# SHT10-Adapter.net
KiCad netlist of a schematic drawn in EAGLE
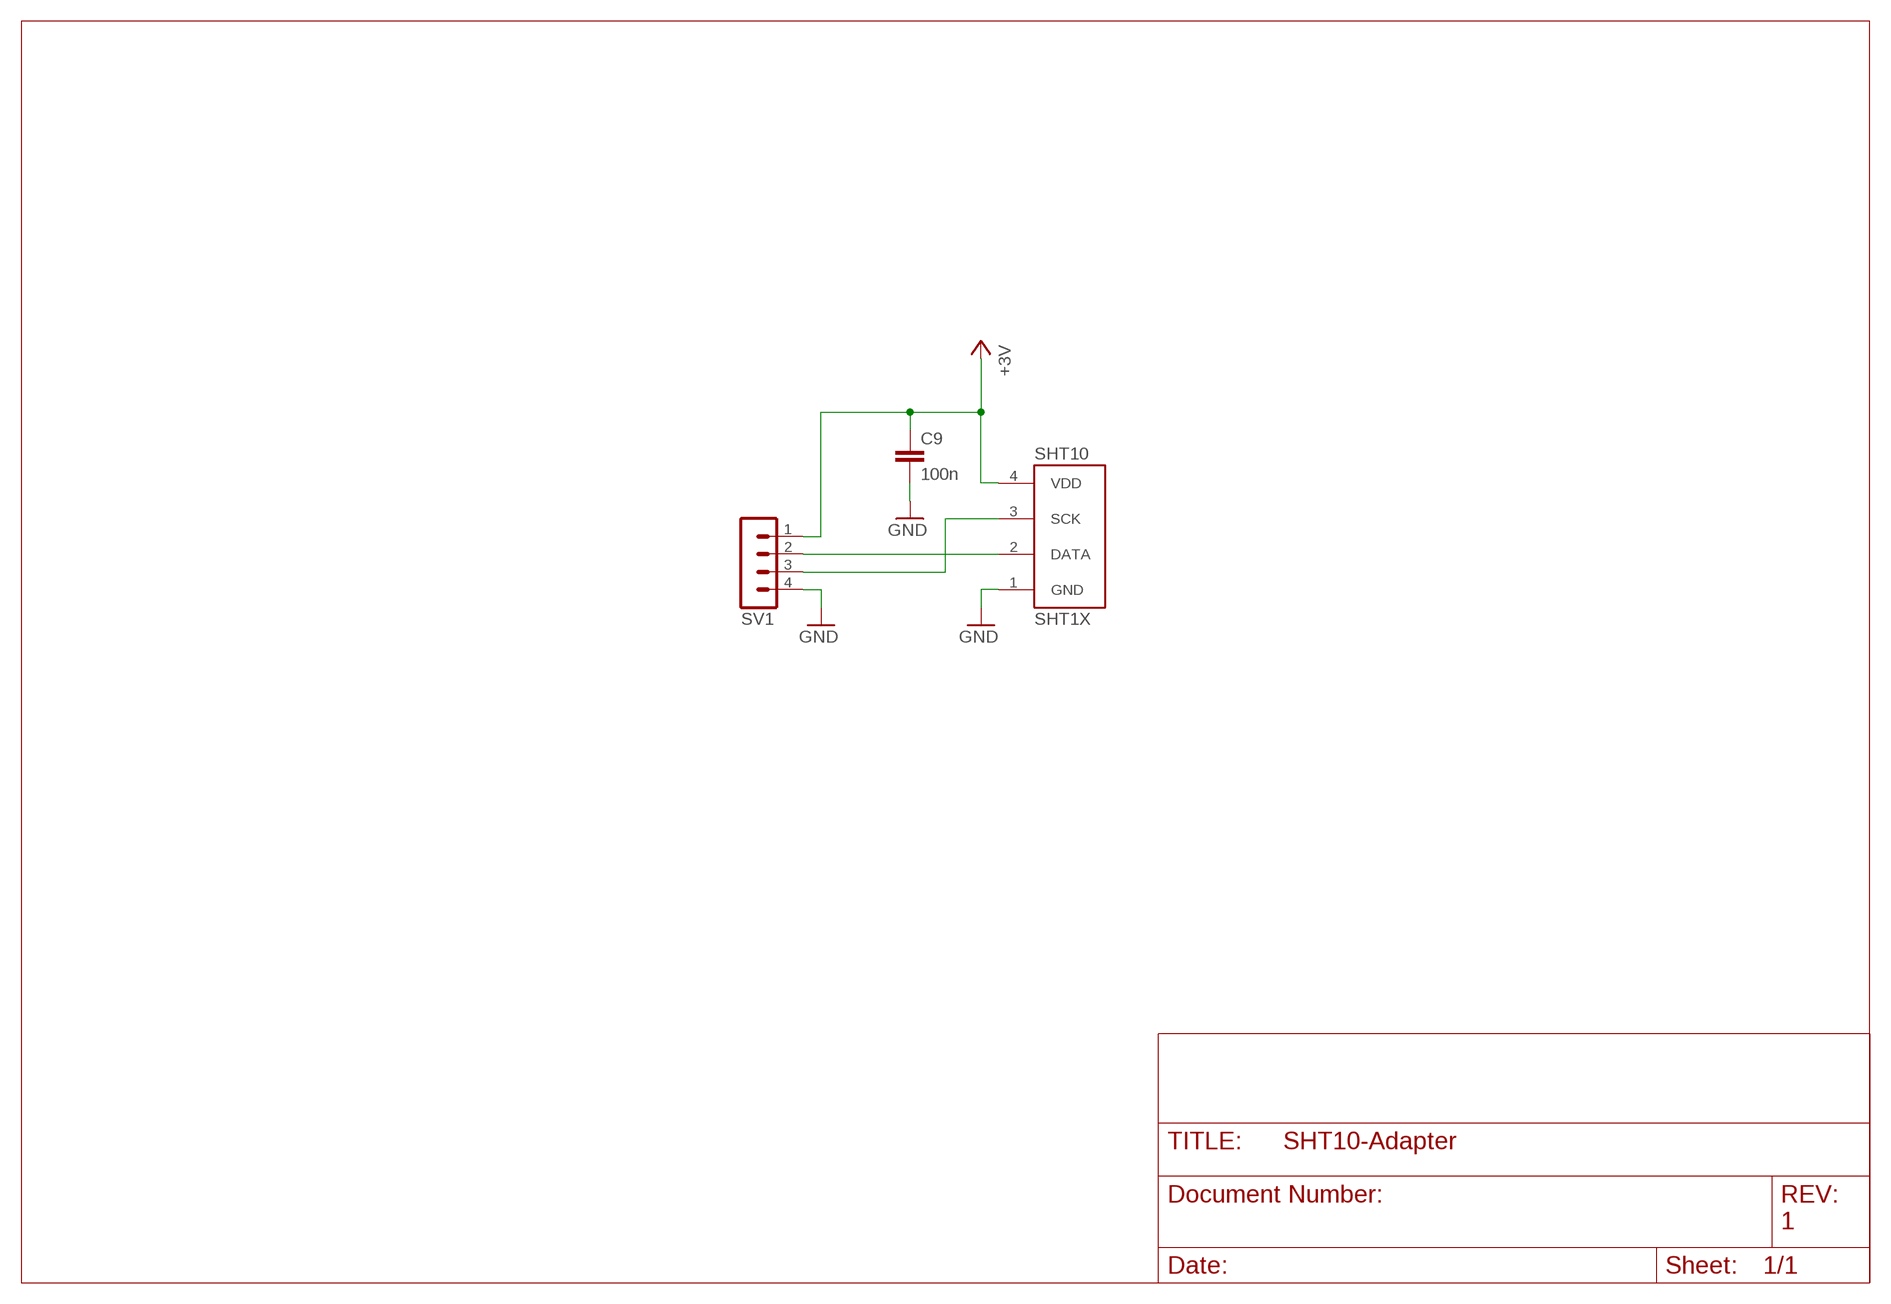
[diagram p0: schematic, sheet 1]

(export (version "E")
  (design (tool "Eeschema 10.0.6"))
  (components
    (comp (ref "C9")
      (value "100n")
      (footprint "eagle-import:C0805")
      (libsource (lib "eagle-import") (part "C-EUC0805"))
    )
    (comp (ref "SHT10")
      (value "SHT1X")
      (footprint "eagle-import:SHT1X")
      (libsource (lib "eagle-import") (part "SHT1X"))
    )
    (comp (ref "SV1")
      (value "MA04-1")
      (footprint "eagle-import:MA04-1")
      (libsource (lib "eagle-import") (part "MA04-1"))
    )
  )
  (nets
    (net (code "1") (name "+3V") (class "Default")
      (node (ref "C9") (pin "1") (pinfunction "1_1") (pintype "passive"))
      (node (ref "SHT10") (pin "4") (pinfunction "VDD_4") (pintype "power_in"))
      (node (ref "SV1") (pin "1") (pinfunction "1_1") (pintype "passive"))
    )
    (net (code "2") (name "GND") (class "Default")
      (node (ref "C9") (pin "2") (pinfunction "2_2") (pintype "passive"))
      (node (ref "SHT10") (pin "1") (pinfunction "GND_1") (pintype "power_in"))
      (node (ref "SV1") (pin "4") (pinfunction "4_4") (pintype "passive"))
    )
    (net (code "3") (name "Net-(SHT10-DATA)") (class "Default")
      (node (ref "SHT10") (pin "2") (pinfunction "DATA_2") (pintype "open_collector"))
      (node (ref "SV1") (pin "2") (pinfunction "2_2") (pintype "passive"))
    )
    (net (code "4") (name "Net-(SHT10-SCK)") (class "Default")
      (node (ref "SHT10") (pin "3") (pinfunction "SCK_3") (pintype "input"))
      (node (ref "SV1") (pin "3") (pinfunction "3_3") (pintype "passive"))
    )
  )
)
